# jtag-isolator.net
KiCad netlist of a schematic drawn in Altium Designer
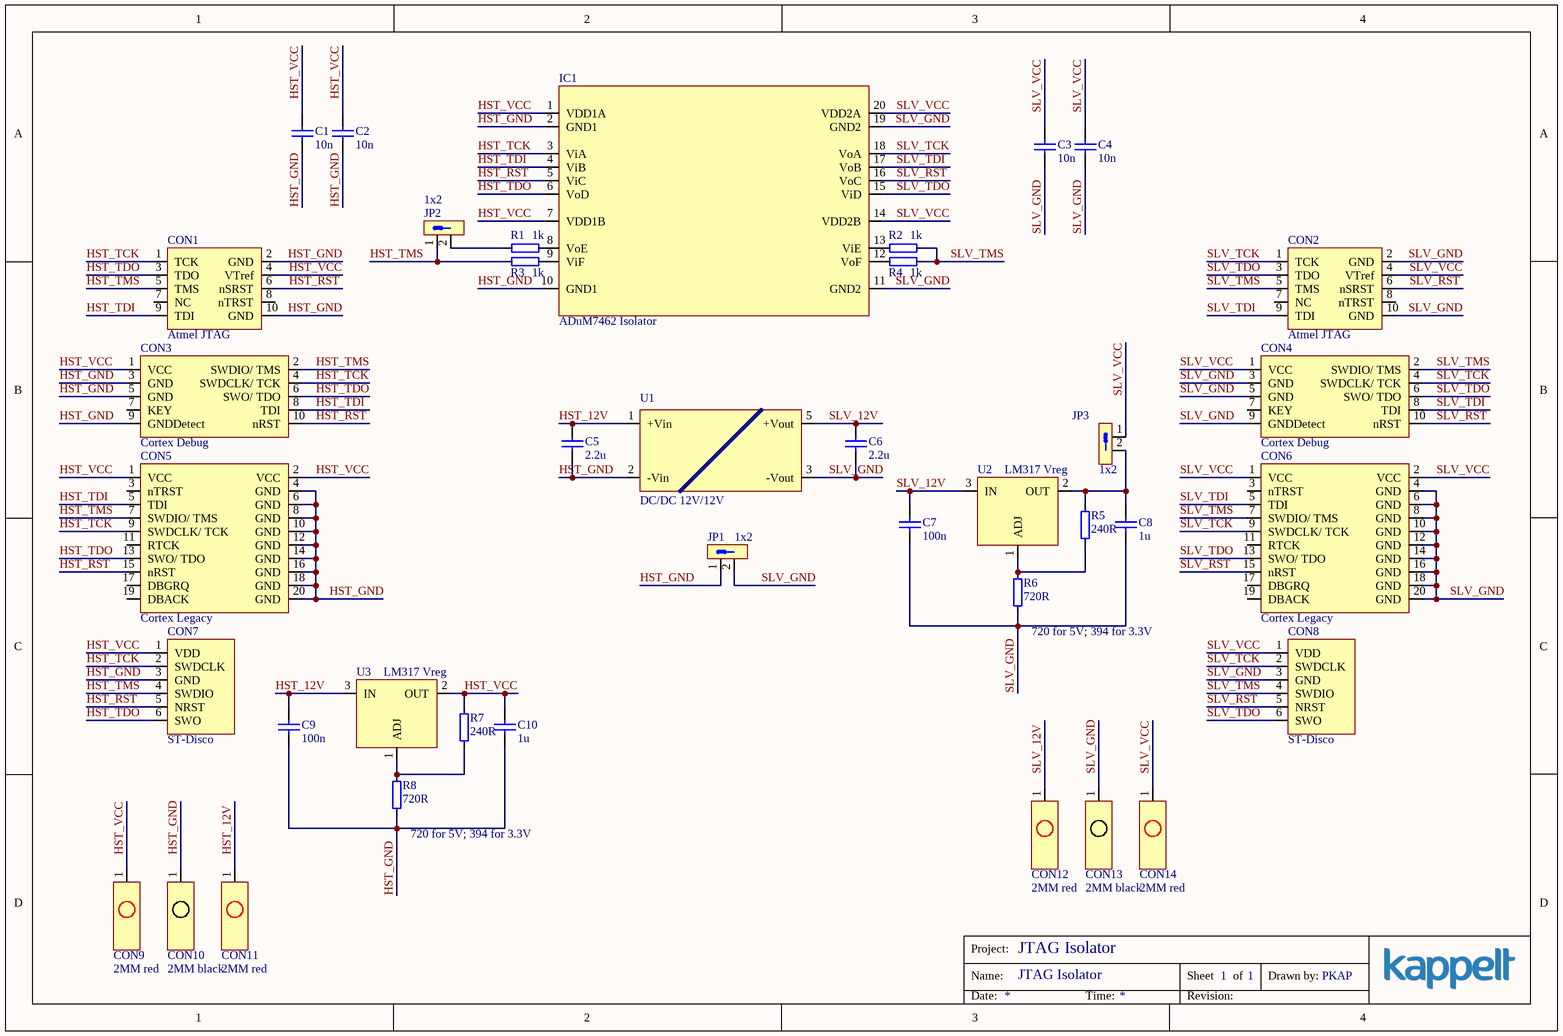
[diagram p0: jtag-isolator.SchDoc]

(export (version "E")
  (design (tool "Eeschema 10.0.6"))
  (components
    (comp (ref "C1")
      (value "10n")
      (footprint "0603_N")
      (description "10n 50V 0603")
      (fields (field (name "PART NUMBER") "10n_50V_0603"))
      (libsource (lib "kappelt_altlib") (part "CAP_CERAMIC"))
    )
    (comp (ref "C2")
      (value "10n")
      (footprint "0603_N")
      (description "10n 50V 0603")
      (fields (field (name "PART NUMBER") "10n_50V_0603"))
      (libsource (lib "kappelt_altlib") (part "CAP_CERAMIC"))
    )
    (comp (ref "C3")
      (value "10n")
      (footprint "0603_N")
      (description "10n 50V 0603")
      (fields (field (name "PART NUMBER") "10n_50V_0603"))
      (libsource (lib "kappelt_altlib") (part "CAP_CERAMIC"))
    )
    (comp (ref "C4")
      (value "10n")
      (footprint "0603_N")
      (description "10n 50V 0603")
      (fields (field (name "PART NUMBER") "10n_50V_0603"))
      (libsource (lib "kappelt_altlib") (part "CAP_CERAMIC"))
    )
    (comp (ref "C5")
      (value "2.2u")
      (footprint "0603_N")
      (description "2u2 25V 0603")
      (fields (field (name "PART NUMBER") "2u2_25V_0603"))
      (libsource (lib "kappelt_altlib") (part "CAP_CERAMIC"))
    )
    (comp (ref "C6")
      (value "2.2u")
      (footprint "0603_N")
      (description "2u2 25V 0603")
      (fields (field (name "PART NUMBER") "2u2_25V_0603"))
      (libsource (lib "kappelt_altlib") (part "CAP_CERAMIC"))
    )
    (comp (ref "C7")
      (value "100n")
      (footprint "0603_N")
      (description "100n 50V 0603")
      (fields (field (name "PART NUMBER") "100n_50V_0603"))
      (libsource (lib "kappelt_altlib") (part "CAP_CERAMIC"))
    )
    (comp (ref "C8")
      (value "1u")
      (footprint "0603_N")
      (description "1u 50V 0603")
      (fields (field (name "PART NUMBER") "1u_50V_0603"))
      (libsource (lib "kappelt_altlib") (part "CAP_CERAMIC"))
    )
    (comp (ref "C9")
      (value "100n")
      (footprint "0603_N")
      (description "100n 50V 0603")
      (fields (field (name "PART NUMBER") "100n_50V_0603"))
      (libsource (lib "kappelt_altlib") (part "CAP_CERAMIC"))
    )
    (comp (ref "C10")
      (value "1u")
      (footprint "0603_N")
      (description "1u 50V 0603")
      (fields (field (name "PART NUMBER") "1u_50V_0603"))
      (libsource (lib "kappelt_altlib") (part "CAP_CERAMIC"))
    )
    (comp (ref "CON1")
      (value "Atmel JTAG")
      (footprint "jtag-isolator:Atmel-JTAG")
      (description "Atmel JTAG Connector")
      (libsource (lib "jtag-isolator") (part "Atmel-JTAG"))
    )
    (comp (ref "CON2")
      (value "Atmel JTAG")
      (footprint "jtag-isolator:Atmel-JTAG")
      (description "Atmel JTAG Connector")
      (libsource (lib "jtag-isolator") (part "Atmel-JTAG"))
    )
    (comp (ref "CON3")
      (value "Cortex Debug")
      (footprint "jtag-isolator:cortex-dbg")
      (libsource (lib "jtag-isolator") (part "Cortex-DBG"))
    )
    (comp (ref "CON4")
      (value "Cortex Debug")
      (footprint "jtag-isolator:cortex-dbg")
      (libsource (lib "jtag-isolator") (part "Cortex-DBG"))
    )
    (comp (ref "CON5")
      (value "Cortex Legacy")
      (footprint "jtag-isolator:Cortex-Legacy")
      (libsource (lib "jtag-isolator") (part "Cortex-Legacy"))
    )
    (comp (ref "CON6")
      (value "Cortex Legacy")
      (footprint "jtag-isolator:Cortex-Legacy")
      (libsource (lib "jtag-isolator") (part "Cortex-Legacy"))
    )
    (comp (ref "CON7")
      (value "ST-Disco")
      (footprint "jtag-isolator:ST-Disco")
      (description "STM Discovery Board JTAG Connector")
      (libsource (lib "jtag-isolator") (part "ST-Disco-SWD"))
    )
    (comp (ref "CON8")
      (value "ST-Disco")
      (footprint "jtag-isolator:ST-Disco")
      (description "STM Discovery Board JTAG Connector")
      (libsource (lib "jtag-isolator") (part "ST-Disco-SWD"))
    )
    (comp (ref "CON9")
      (value "2MM red")
      (footprint "jtag-isolator:MPB1-Red")
      (description "2MM test connector")
      (libsource (lib "jtag-isolator") (part "2MM-Red"))
    )
    (comp (ref "CON10")
      (value "2MM black")
      (footprint "jtag-isolator:MPB1-Black")
      (description "2MM test connector")
      (libsource (lib "jtag-isolator") (part "2MM-Black"))
    )
    (comp (ref "CON11")
      (value "2MM red")
      (footprint "jtag-isolator:MPB1-Red")
      (description "2MM test connector")
      (libsource (lib "jtag-isolator") (part "2MM-Red"))
    )
    (comp (ref "CON12")
      (value "2MM red")
      (footprint "jtag-isolator:MPB1-Red")
      (description "2MM test connector")
      (libsource (lib "jtag-isolator") (part "2MM-Red"))
    )
    (comp (ref "CON13")
      (value "2MM black")
      (footprint "jtag-isolator:MPB1-Black")
      (description "2MM test connector")
      (libsource (lib "jtag-isolator") (part "2MM-Black"))
    )
    (comp (ref "CON14")
      (value "2MM red")
      (footprint "jtag-isolator:MPB1-Red")
      (description "2MM test connector")
      (libsource (lib "jtag-isolator") (part "2MM-Red"))
    )
    (comp (ref "IC1")
      (value "ADuM7462 Isolator")
      (footprint "jtag-isolator:ADUM7462-QSOP20")
      (description "1 kV RMS Six-Channel Digital Isolators")
      (libsource (lib "jtag-isolator") (part "ADuM7642"))
    )
    (comp (ref "JP1")
      (value "1x2")
      (footprint "Header_254_1x2_male")
      (description "Male Connector 1x2")
      (fields (field (name "PART NUMBER") "Header_1x02_male"))
      (libsource (lib "") (part "Header_1X02_male_1"))
    )
    (comp (ref "JP2")
      (value "1x2")
      (footprint "Header_254_1x2_male")
      (description "Male Connector 1x2")
      (fields (field (name "PART NUMBER") "Header_1x02_male"))
      (libsource (lib "") (part "Header_1X02_male_1"))
    )
    (comp (ref "JP3")
      (value "1x2")
      (footprint "Header_254_1x2_male")
      (description "Male Connector 1x2")
      (fields (field (name "PART NUMBER") "Header_1x02_male"))
      (libsource (lib "kappelt_altlib") (part "Header_1X02_male"))
    )
    (comp (ref "R1")
      (value "1k")
      (footprint "0603_N")
      (description "1k 100mW 0603")
      (fields (field (name "PART NUMBER") "1k_100mW_0603"))
      (libsource (lib "kappelt_altlib") (part "RESISTOR"))
    )
    (comp (ref "R2")
      (value "1k")
      (footprint "0603_N")
      (description "1k 100mW 0603")
      (fields (field (name "PART NUMBER") "1k_100mW_0603"))
      (libsource (lib "kappelt_altlib") (part "RESISTOR"))
    )
    (comp (ref "R3")
      (value "1k")
      (footprint "0603_N")
      (description "1k 100mW 0603")
      (fields (field (name "PART NUMBER") "1k_100mW_0603"))
      (libsource (lib "kappelt_altlib") (part "RESISTOR"))
    )
    (comp (ref "R4")
      (value "1k")
      (footprint "0603_N")
      (description "1k 100mW 0603")
      (fields (field (name "PART NUMBER") "1k_100mW_0603"))
      (libsource (lib "kappelt_altlib") (part "RESISTOR"))
    )
    (comp (ref "R5")
      (value "240R")
      (footprint "0603_N")
      (description "240R 100mW 0603")
      (fields (field (name "PART NUMBER") "240R_100mW_0603"))
      (libsource (lib "kappelt_altlib") (part "RESISTOR"))
    )
    (comp (ref "R6")
      (value "720R")
      (footprint "0603_N")
      (description "720R 100mW 0603")
      (fields (field (name "PART NUMBER") "720R_100mW_0603"))
      (libsource (lib "kappelt_altlib") (part "RESISTOR"))
    )
    (comp (ref "R7")
      (value "240R")
      (footprint "0603_N")
      (description "240R 100mW 0603")
      (fields (field (name "PART NUMBER") "240R_100mW_0603"))
      (libsource (lib "kappelt_altlib") (part "RESISTOR"))
    )
    (comp (ref "R8")
      (value "720R")
      (footprint "0603_N")
      (description "720R 100mW 0603")
      (fields (field (name "PART NUMBER") "720R_100mW_0603"))
      (libsource (lib "kappelt_altlib") (part "RESISTOR"))
    )
    (comp (ref "U1")
      (value "DC/DC 12V/12V")
      (footprint "jtag-isolator:TMA-1212S")
      (description "Isolierter DC/DC-Wandler f. PCB-Montage, Fest, 1 Ausgang, 10.8 V, 13.2 V, 1 W, 12 V")
      (libsource (lib "jtag-isolator") (part "TMA-1212S"))
    )
    (comp (ref "U2")
      (value "LM317 Vreg")
      (footprint "jtag-isolator:LM317-SOT223")
      (description "Linear Voltage Regulator, Adjustable, 40V primary input, 1.25V to 37V/1.5A/1 Output, SOT-223-4")
      (libsource (lib "jtag-isolator") (part "LM317DCY"))
    )
    (comp (ref "U3")
      (value "LM317 Vreg")
      (footprint "jtag-isolator:LM317-SOT223")
      (description "Linear Voltage Regulator, Adjustable, 40V primary input, 1.25V to 37V/1.5A/1 Output, SOT-223-4")
      (libsource (lib "jtag-isolator") (part "LM317DCY"))
    )
  )
  (nets
    (net (code "1") (name "/HST_12V") (class "Default")
      (node (ref "C5") (pin "2") (pinfunction "2_2") (pintype "passive"))
      (node (ref "C9") (pin "2") (pinfunction "2_2") (pintype "passive"))
      (node (ref "CON11") (pin "1") (pinfunction "1_1") (pintype "passive"))
      (node (ref "U1") (pin "1") (pinfunction "+Vin_1") (pintype "passive"))
      (node (ref "U3") (pin "3") (pinfunction "IN_3") (pintype "passive"))
    )
    (net (code "2") (name "/HST_GND") (class "Default")
      (node (ref "C1") (pin "1") (pinfunction "1_1") (pintype "passive"))
      (node (ref "C10") (pin "1") (pinfunction "1_1") (pintype "passive"))
      (node (ref "C2") (pin "1") (pinfunction "1_1") (pintype "passive"))
      (node (ref "C5") (pin "1") (pinfunction "1_1") (pintype "passive"))
      (node (ref "C9") (pin "1") (pinfunction "1_1") (pintype "passive"))
      (node (ref "CON1") (pin "10") (pinfunction "GND_10") (pintype "passive"))
      (node (ref "CON1") (pin "2") (pinfunction "GND_2") (pintype "passive"))
      (node (ref "CON10") (pin "1") (pinfunction "1_1") (pintype "passive"))
      (node (ref "CON3") (pin "3") (pinfunction "GND_3") (pintype "passive"))
      (node (ref "CON3") (pin "5") (pinfunction "GND_5") (pintype "passive"))
      (node (ref "CON3") (pin "9") (pinfunction "GNDDetect_9") (pintype "passive"))
      (node (ref "CON5") (pin "10") (pinfunction "GND_10") (pintype "passive"))
      (node (ref "CON5") (pin "12") (pinfunction "GND_12") (pintype "passive"))
      (node (ref "CON5") (pin "14") (pinfunction "GND_14") (pintype "passive"))
      (node (ref "CON5") (pin "16") (pinfunction "GND_16") (pintype "passive"))
      (node (ref "CON5") (pin "18") (pinfunction "GND_18") (pintype "passive"))
      (node (ref "CON5") (pin "20") (pinfunction "GND_20") (pintype "passive"))
      (node (ref "CON5") (pin "4") (pinfunction "GND_4") (pintype "passive"))
      (node (ref "CON5") (pin "6") (pinfunction "GND_6") (pintype "passive"))
      (node (ref "CON5") (pin "8") (pinfunction "GND_8") (pintype "passive"))
      (node (ref "CON7") (pin "3") (pinfunction "GND_3") (pintype "passive"))
      (node (ref "IC1") (pin "10") (pinfunction "GND1_10") (pintype "passive"))
      (node (ref "IC1") (pin "2") (pinfunction "GND1_2") (pintype "passive"))
      (node (ref "JP1") (pin "1") (pinfunction "1_1") (pintype "passive"))
      (node (ref "R8") (pin "2") (pintype "passive"))
      (node (ref "U1") (pin "2") (pinfunction "-Vin_2") (pintype "passive"))
    )
    (net (code "3") (name "/HST_RST") (class "Default")
      (node (ref "CON1") (pin "6") (pinfunction "nSRST_6") (pintype "passive"))
      (node (ref "CON3") (pin "10") (pinfunction "nRST_10") (pintype "passive"))
      (node (ref "CON5") (pin "15") (pinfunction "nRST_15") (pintype "passive"))
      (node (ref "CON7") (pin "5") (pinfunction "NRST_5") (pintype "passive"))
      (node (ref "IC1") (pin "5") (pinfunction "ViC_5") (pintype "passive"))
    )
    (net (code "4") (name "/HST_TCK") (class "Default")
      (node (ref "CON1") (pin "1") (pinfunction "TCK_1") (pintype "passive"))
      (node (ref "CON3") (pin "4") (pinfunction "SWDCLK/_TCK_4") (pintype "passive"))
      (node (ref "CON5") (pin "9") (pinfunction "SWDCLK/_TCK_9") (pintype "passive"))
      (node (ref "CON7") (pin "2") (pinfunction "SWDCLK_2") (pintype "passive"))
      (node (ref "IC1") (pin "3") (pinfunction "ViA_3") (pintype "passive"))
    )
    (net (code "5") (name "/HST_TDI") (class "Default")
      (node (ref "CON1") (pin "9") (pinfunction "TDI_9") (pintype "passive"))
      (node (ref "CON3") (pin "8") (pinfunction "TDI_8") (pintype "passive"))
      (node (ref "CON5") (pin "5") (pinfunction "TDI_5") (pintype "passive"))
      (node (ref "IC1") (pin "4") (pinfunction "ViB_4") (pintype "passive"))
    )
    (net (code "6") (name "/HST_TDO") (class "Default")
      (node (ref "CON1") (pin "3") (pinfunction "TDO_3") (pintype "passive"))
      (node (ref "CON3") (pin "6") (pinfunction "SWO/_TDO_6") (pintype "passive"))
      (node (ref "CON5") (pin "13") (pinfunction "SWO/_TDO_13") (pintype "passive"))
      (node (ref "CON7") (pin "6") (pinfunction "SWO_6") (pintype "passive"))
      (node (ref "IC1") (pin "6") (pinfunction "VoD_6") (pintype "passive"))
    )
    (net (code "7") (name "/HST_TMS") (class "Default")
      (node (ref "CON1") (pin "5") (pinfunction "TMS_5") (pintype "passive"))
      (node (ref "CON3") (pin "2") (pinfunction "SWDIO/_TMS_2") (pintype "passive"))
      (node (ref "CON5") (pin "7") (pinfunction "SWDIO/_TMS_7") (pintype "passive"))
      (node (ref "CON7") (pin "4") (pinfunction "SWDIO_4") (pintype "passive"))
      (node (ref "JP2") (pin "1") (pinfunction "1_1") (pintype "passive"))
      (node (ref "R3") (pin "2") (pintype "passive"))
    )
    (net (code "8") (name "/HST_VCC") (class "Default")
      (node (ref "C1") (pin "2") (pinfunction "2_2") (pintype "passive"))
      (node (ref "C10") (pin "2") (pinfunction "2_2") (pintype "passive"))
      (node (ref "C2") (pin "2") (pinfunction "2_2") (pintype "passive"))
      (node (ref "CON1") (pin "4") (pinfunction "VTref_4") (pintype "passive"))
      (node (ref "CON3") (pin "1") (pinfunction "VCC_1") (pintype "passive"))
      (node (ref "CON5") (pin "1") (pinfunction "VCC_1") (pintype "passive"))
      (node (ref "CON5") (pin "2") (pinfunction "VCC_2") (pintype "passive"))
      (node (ref "CON7") (pin "1") (pinfunction "VDD_1") (pintype "passive"))
      (node (ref "CON9") (pin "1") (pinfunction "1_1") (pintype "passive"))
      (node (ref "IC1") (pin "1") (pinfunction "VDD1A_1") (pintype "passive"))
      (node (ref "IC1") (pin "7") (pinfunction "VDD1B_7") (pintype "passive"))
      (node (ref "R7") (pin "1") (pintype "passive"))
      (node (ref "U3") (pin "2") (pinfunction "OUT_2") (pintype "passive"))
    )
    (net (code "9") (name "/SLV_12V") (class "Default")
      (node (ref "C6") (pin "2") (pinfunction "2_2") (pintype "passive"))
      (node (ref "C7") (pin "2") (pinfunction "2_2") (pintype "passive"))
      (node (ref "CON12") (pin "1") (pinfunction "1_1") (pintype "passive"))
      (node (ref "U1") (pin "5") (pinfunction "+Vout_5") (pintype "passive"))
      (node (ref "U2") (pin "3") (pinfunction "IN_3") (pintype "passive"))
    )
    (net (code "10") (name "/SLV_GND") (class "Default")
      (node (ref "C3") (pin "1") (pinfunction "1_1") (pintype "passive"))
      (node (ref "C4") (pin "1") (pinfunction "1_1") (pintype "passive"))
      (node (ref "C6") (pin "1") (pinfunction "1_1") (pintype "passive"))
      (node (ref "C7") (pin "1") (pinfunction "1_1") (pintype "passive"))
      (node (ref "C8") (pin "1") (pinfunction "1_1") (pintype "passive"))
      (node (ref "CON13") (pin "1") (pinfunction "1_1") (pintype "passive"))
      (node (ref "CON2") (pin "10") (pinfunction "GND_10") (pintype "passive"))
      (node (ref "CON2") (pin "2") (pinfunction "GND_2") (pintype "passive"))
      (node (ref "CON4") (pin "3") (pinfunction "GND_3") (pintype "passive"))
      (node (ref "CON4") (pin "5") (pinfunction "GND_5") (pintype "passive"))
      (node (ref "CON4") (pin "9") (pinfunction "GNDDetect_9") (pintype "passive"))
      (node (ref "CON6") (pin "10") (pinfunction "GND_10") (pintype "passive"))
      (node (ref "CON6") (pin "12") (pinfunction "GND_12") (pintype "passive"))
      (node (ref "CON6") (pin "14") (pinfunction "GND_14") (pintype "passive"))
      (node (ref "CON6") (pin "16") (pinfunction "GND_16") (pintype "passive"))
      (node (ref "CON6") (pin "18") (pinfunction "GND_18") (pintype "passive"))
      (node (ref "CON6") (pin "20") (pinfunction "GND_20") (pintype "passive"))
      (node (ref "CON6") (pin "4") (pinfunction "GND_4") (pintype "passive"))
      (node (ref "CON6") (pin "6") (pinfunction "GND_6") (pintype "passive"))
      (node (ref "CON6") (pin "8") (pinfunction "GND_8") (pintype "passive"))
      (node (ref "CON8") (pin "3") (pinfunction "GND_3") (pintype "passive"))
      (node (ref "IC1") (pin "11") (pinfunction "GND2_11") (pintype "passive"))
      (node (ref "IC1") (pin "19") (pinfunction "GND2_19") (pintype "passive"))
      (node (ref "JP1") (pin "2") (pinfunction "2_2") (pintype "passive"))
      (node (ref "R6") (pin "2") (pintype "passive"))
      (node (ref "U1") (pin "3") (pinfunction "-Vout_3") (pintype "passive"))
    )
    (net (code "11") (name "/SLV_RST") (class "Default")
      (node (ref "CON2") (pin "6") (pinfunction "nSRST_6") (pintype "passive"))
      (node (ref "CON4") (pin "10") (pinfunction "nRST_10") (pintype "passive"))
      (node (ref "CON6") (pin "15") (pinfunction "nRST_15") (pintype "passive"))
      (node (ref "CON8") (pin "5") (pinfunction "NRST_5") (pintype "passive"))
      (node (ref "IC1") (pin "16") (pinfunction "VoC_16") (pintype "passive"))
    )
    (net (code "12") (name "/SLV_TCK") (class "Default")
      (node (ref "CON2") (pin "1") (pinfunction "TCK_1") (pintype "passive"))
      (node (ref "CON4") (pin "4") (pinfunction "SWDCLK/_TCK_4") (pintype "passive"))
      (node (ref "CON6") (pin "9") (pinfunction "SWDCLK/_TCK_9") (pintype "passive"))
      (node (ref "CON8") (pin "2") (pinfunction "SWDCLK_2") (pintype "passive"))
      (node (ref "IC1") (pin "18") (pinfunction "VoA_18") (pintype "passive"))
    )
    (net (code "13") (name "/SLV_TDI") (class "Default")
      (node (ref "CON2") (pin "9") (pinfunction "TDI_9") (pintype "passive"))
      (node (ref "CON4") (pin "8") (pinfunction "TDI_8") (pintype "passive"))
      (node (ref "CON6") (pin "5") (pinfunction "TDI_5") (pintype "passive"))
      (node (ref "IC1") (pin "17") (pinfunction "VoB_17") (pintype "passive"))
    )
    (net (code "14") (name "/SLV_TDO") (class "Default")
      (node (ref "CON2") (pin "3") (pinfunction "TDO_3") (pintype "passive"))
      (node (ref "CON4") (pin "6") (pinfunction "SWO/_TDO_6") (pintype "passive"))
      (node (ref "CON6") (pin "13") (pinfunction "SWO/_TDO_13") (pintype "passive"))
      (node (ref "CON8") (pin "6") (pinfunction "SWO_6") (pintype "passive"))
      (node (ref "IC1") (pin "15") (pinfunction "ViD_15") (pintype "passive"))
    )
    (net (code "15") (name "/SLV_TMS") (class "Default")
      (node (ref "CON2") (pin "5") (pinfunction "TMS_5") (pintype "passive"))
      (node (ref "CON4") (pin "2") (pinfunction "SWDIO/_TMS_2") (pintype "passive"))
      (node (ref "CON6") (pin "7") (pinfunction "SWDIO/_TMS_7") (pintype "passive"))
      (node (ref "CON8") (pin "4") (pinfunction "SWDIO_4") (pintype "passive"))
      (node (ref "R2") (pin "1") (pintype "passive"))
      (node (ref "R4") (pin "1") (pintype "passive"))
    )
    (net (code "16") (name "/SLV_VCC") (class "Default")
      (node (ref "C3") (pin "2") (pinfunction "2_2") (pintype "passive"))
      (node (ref "C4") (pin "2") (pinfunction "2_2") (pintype "passive"))
      (node (ref "CON14") (pin "1") (pinfunction "1_1") (pintype "passive"))
      (node (ref "CON2") (pin "4") (pinfunction "VTref_4") (pintype "passive"))
      (node (ref "CON4") (pin "1") (pinfunction "VCC_1") (pintype "passive"))
      (node (ref "CON6") (pin "1") (pinfunction "VCC_1") (pintype "passive"))
      (node (ref "CON6") (pin "2") (pinfunction "VCC_2") (pintype "passive"))
      (node (ref "CON8") (pin "1") (pinfunction "VDD_1") (pintype "passive"))
      (node (ref "IC1") (pin "14") (pinfunction "VDD2B_14") (pintype "passive"))
      (node (ref "IC1") (pin "20") (pinfunction "VDD2A_20") (pintype "passive"))
      (node (ref "JP3") (pin "1") (pinfunction "1_1") (pintype "passive"))
    )
    (net (code "17") (name "Net-(IC1-ViE)") (class "Default")
      (node (ref "IC1") (pin "13") (pinfunction "ViE_13") (pintype "passive"))
      (node (ref "R2") (pin "2") (pintype "passive"))
    )
    (net (code "18") (name "Net-(IC1-ViF)") (class "Default")
      (node (ref "IC1") (pin "9") (pinfunction "ViF_9") (pintype "passive"))
      (node (ref "R3") (pin "1") (pintype "passive"))
    )
    (net (code "19") (name "Net-(IC1-VoE)") (class "Default")
      (node (ref "IC1") (pin "8") (pinfunction "VoE_8") (pintype "passive"))
      (node (ref "R1") (pin "1") (pintype "passive"))
    )
    (net (code "20") (name "Net-(IC1-VoF)") (class "Default")
      (node (ref "IC1") (pin "12") (pinfunction "VoF_12") (pintype "passive"))
      (node (ref "R4") (pin "2") (pintype "passive"))
    )
    (net (code "21") (name "Net-(JP2-Pad2)") (class "Default")
      (node (ref "JP2") (pin "2") (pinfunction "2_2") (pintype "passive"))
      (node (ref "R1") (pin "2") (pintype "passive"))
    )
    (net (code "22") (name "Net-(U2-ADJ)") (class "Default")
      (node (ref "R5") (pin "2") (pintype "passive"))
      (node (ref "R6") (pin "1") (pintype "passive"))
      (node (ref "U2") (pin "1") (pinfunction "ADJ_1") (pintype "passive"))
    )
    (net (code "23") (name "Net-(U2-OUT)") (class "Default")
      (node (ref "C8") (pin "2") (pinfunction "2_2") (pintype "passive"))
      (node (ref "JP3") (pin "2") (pinfunction "2_2") (pintype "passive"))
      (node (ref "R5") (pin "1") (pintype "passive"))
      (node (ref "U2") (pin "2") (pinfunction "OUT_2") (pintype "passive"))
    )
    (net (code "24") (name "Net-(U3-ADJ)") (class "Default")
      (node (ref "R7") (pin "2") (pintype "passive"))
      (node (ref "R8") (pin "1") (pintype "passive"))
      (node (ref "U3") (pin "1") (pinfunction "ADJ_1") (pintype "passive"))
    )
    (net (code "25") (name "unconnected-(CON1-NC-Pad7)") (class "Default")
      (node (ref "CON1") (pin "7") (pinfunction "NC_7") (pintype "passive"))
    )
    (net (code "26") (name "unconnected-(CON1-nTRST-Pad8)") (class "Default")
      (node (ref "CON1") (pin "8") (pinfunction "nTRST_8") (pintype "passive"))
    )
    (net (code "27") (name "unconnected-(CON2-NC-Pad7)") (class "Default")
      (node (ref "CON2") (pin "7") (pinfunction "NC_7") (pintype "passive"))
    )
    (net (code "28") (name "unconnected-(CON2-nTRST-Pad8)") (class "Default")
      (node (ref "CON2") (pin "8") (pinfunction "nTRST_8") (pintype "passive"))
    )
    (net (code "29") (name "unconnected-(CON3-KEY-Pad7)") (class "Default")
      (node (ref "CON3") (pin "7") (pinfunction "KEY_7") (pintype "passive"))
    )
    (net (code "30") (name "unconnected-(CON4-KEY-Pad7)") (class "Default")
      (node (ref "CON4") (pin "7") (pinfunction "KEY_7") (pintype "passive"))
    )
    (net (code "31") (name "unconnected-(CON5-DBACK-Pad19)") (class "Default")
      (node (ref "CON5") (pin "19") (pinfunction "DBACK_19") (pintype "passive"))
    )
    (net (code "32") (name "unconnected-(CON5-DBGRQ-Pad17)") (class "Default")
      (node (ref "CON5") (pin "17") (pinfunction "DBGRQ_17") (pintype "passive"))
    )
    (net (code "33") (name "unconnected-(CON5-RTCK-Pad11)") (class "Default")
      (node (ref "CON5") (pin "11") (pinfunction "RTCK_11") (pintype "passive"))
    )
    (net (code "34") (name "unconnected-(CON5-nTRST-Pad3)") (class "Default")
      (node (ref "CON5") (pin "3") (pinfunction "nTRST_3") (pintype "passive"))
    )
    (net (code "35") (name "unconnected-(CON6-DBACK-Pad19)") (class "Default")
      (node (ref "CON6") (pin "19") (pinfunction "DBACK_19") (pintype "passive"))
    )
    (net (code "36") (name "unconnected-(CON6-DBGRQ-Pad17)") (class "Default")
      (node (ref "CON6") (pin "17") (pinfunction "DBGRQ_17") (pintype "passive"))
    )
    (net (code "37") (name "unconnected-(CON6-RTCK-Pad11)") (class "Default")
      (node (ref "CON6") (pin "11") (pinfunction "RTCK_11") (pintype "passive"))
    )
    (net (code "38") (name "unconnected-(CON6-nTRST-Pad3)") (class "Default")
      (node (ref "CON6") (pin "3") (pinfunction "nTRST_3") (pintype "passive"))
    )
  )
)
